# chrl.net
KiCad netlist of a schematic drawn in EAGLE
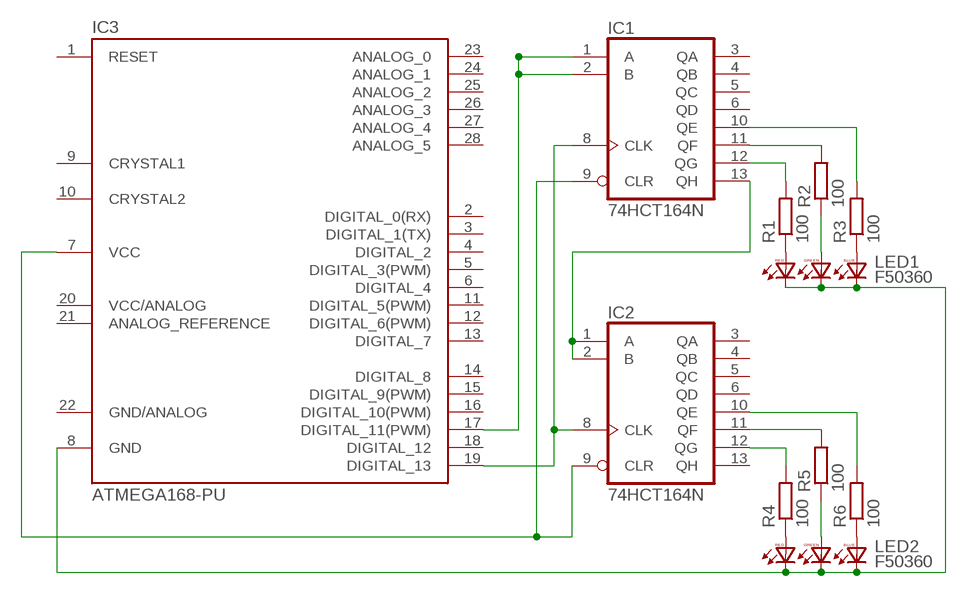
[diagram p0: schematic, sheet 1]

(export (version "E")
  (design (tool "Eeschema 10.0.6"))
  (components
    (comp (ref "IC1")
      (value "74HCT164N")
      (footprint "eagle-import:DIL14")
      (libsource (lib "eagle-import") (part "74164NHCT"))
    )
    (comp (ref "IC2")
      (value "74HCT164N")
      (footprint "eagle-import:DIL14")
      (libsource (lib "eagle-import") (part "74164NHCT"))
    )
    (comp (ref "IC3")
      (value "ATMEGA168-PU")
      (footprint "eagle-import:DIL28-3")
      (libsource (lib "eagle-import") (part "ATMEGA168-PU"))
    )
    (comp (ref "LED1")
      (value "F50360")
      (footprint "eagle-import:F50360")
      (libsource (lib "eagle-import") (part "F50360"))
    )
    (comp (ref "LED2")
      (value "F50360")
      (footprint "eagle-import:F50360")
      (libsource (lib "eagle-import") (part "F50360"))
    )
    (comp (ref "R1")
      (value "100")
      (footprint "eagle-import:0204_7")
      (libsource (lib "eagle-import") (part "R-EU_0204/7"))
    )
    (comp (ref "R2")
      (value "100")
      (footprint "eagle-import:0204_7")
      (libsource (lib "eagle-import") (part "R-EU_0204/7"))
    )
    (comp (ref "R3")
      (value "100")
      (footprint "eagle-import:0204_7")
      (libsource (lib "eagle-import") (part "R-EU_0204/7"))
    )
    (comp (ref "R4")
      (value "100")
      (footprint "eagle-import:0204_7")
      (libsource (lib "eagle-import") (part "R-EU_0204/7"))
    )
    (comp (ref "R5")
      (value "100")
      (footprint "eagle-import:0204_7")
      (libsource (lib "eagle-import") (part "R-EU_0204/7"))
    )
    (comp (ref "R6")
      (value "100")
      (footprint "eagle-import:0204_7")
      (libsource (lib "eagle-import") (part "R-EU_0204/7"))
    )
  )
  (nets
    (net (code "1") (name "/GND{slash}ANALOG") (class "Default")
      (node (ref "IC3") (pin "22") (pinfunction "GND/ANALOG_22") (pintype "power_in"))
    )
    (net (code "2") (name "Net-(IC1A-A)") (class "Default")
      (node (ref "IC1") (pin "1") (pinfunction "A_1") (pintype "input"))
      (node (ref "IC1") (pin "2") (pinfunction "B_2") (pintype "input"))
      (node (ref "IC3") (pin "17") (pinfunction "DIGITAL_11(PWM)_17") (pintype "bidirectional"))
    )
    (net (code "3") (name "Net-(IC1A-CLK)") (class "Default")
      (node (ref "IC1") (pin "8") (pinfunction "CLK_8") (pintype "input"))
      (node (ref "IC2") (pin "8") (pinfunction "CLK_8") (pintype "input"))
      (node (ref "IC3") (pin "19") (pinfunction "DIGITAL_13_19") (pintype "bidirectional"))
    )
    (net (code "4") (name "Net-(IC1A-CLR)") (class "Default")
      (node (ref "IC1") (pin "9") (pinfunction "CLR_9") (pintype "input"))
      (node (ref "IC2") (pin "9") (pinfunction "CLR_9") (pintype "input"))
      (node (ref "IC3") (pin "7") (pinfunction "VCC_7") (pintype "power_in"))
    )
    (net (code "5") (name "Net-(IC1A-QE)") (class "Default")
      (node (ref "IC1") (pin "10") (pinfunction "QE_10") (pintype "output"))
      (node (ref "R3") (pin "2") (pinfunction "2_2") (pintype "passive"))
    )
    (net (code "6") (name "Net-(IC1A-QF)") (class "Default")
      (node (ref "IC1") (pin "11") (pinfunction "QF_11") (pintype "output"))
      (node (ref "R2") (pin "2") (pinfunction "2_2") (pintype "passive"))
    )
    (net (code "7") (name "Net-(IC1A-QG)") (class "Default")
      (node (ref "IC1") (pin "12") (pinfunction "QG_12") (pintype "output"))
      (node (ref "R1") (pin "2") (pinfunction "2_2") (pintype "passive"))
    )
    (net (code "8") (name "Net-(IC1A-QH)") (class "Default")
      (node (ref "IC1") (pin "13") (pinfunction "QH_13") (pintype "output"))
      (node (ref "IC2") (pin "1") (pinfunction "A_1") (pintype "input"))
      (node (ref "IC2") (pin "2") (pinfunction "B_2") (pintype "input"))
    )
    (net (code "9") (name "Net-(IC2A-QE)") (class "Default")
      (node (ref "IC2") (pin "10") (pinfunction "QE_10") (pintype "output"))
      (node (ref "R6") (pin "2") (pinfunction "2_2") (pintype "passive"))
    )
    (net (code "10") (name "Net-(IC2A-QF)") (class "Default")
      (node (ref "IC2") (pin "11") (pinfunction "QF_11") (pintype "output"))
      (node (ref "R5") (pin "2") (pinfunction "2_2") (pintype "passive"))
    )
    (net (code "11") (name "Net-(IC2A-QG)") (class "Default")
      (node (ref "IC2") (pin "12") (pinfunction "QG_12") (pintype "output"))
      (node (ref "R4") (pin "2") (pinfunction "2_2") (pintype "passive"))
    )
    (net (code "12") (name "Net-(IC3-GND)") (class "Default")
      (node (ref "IC3") (pin "8") (pinfunction "GND_8") (pintype "power_in"))
      (node (ref "LED1") (pin "BC") (pinfunction "BC_BC") (pintype "passive"))
      (node (ref "LED1") (pin "GC") (pinfunction "GC_GC") (pintype "passive"))
      (node (ref "LED1") (pin "RC") (pinfunction "RC_RC") (pintype "passive"))
      (node (ref "LED2") (pin "BC") (pinfunction "BC_BC") (pintype "passive"))
      (node (ref "LED2") (pin "GC") (pinfunction "GC_GC") (pintype "passive"))
      (node (ref "LED2") (pin "RC") (pinfunction "RC_RC") (pintype "passive"))
    )
    (net (code "13") (name "Net-(LED1-PadBA)") (class "Default")
      (node (ref "LED1") (pin "BA") (pinfunction "BA_BA") (pintype "passive"))
      (node (ref "R3") (pin "1") (pinfunction "1_1") (pintype "passive"))
    )
    (net (code "14") (name "Net-(LED1-PadGA)") (class "Default")
      (node (ref "LED1") (pin "GA") (pinfunction "GA_GA") (pintype "passive"))
      (node (ref "R2") (pin "1") (pinfunction "1_1") (pintype "passive"))
    )
    (net (code "15") (name "Net-(LED1-PadRA)") (class "Default")
      (node (ref "LED1") (pin "RA") (pinfunction "RA_RA") (pintype "passive"))
      (node (ref "R1") (pin "1") (pinfunction "1_1") (pintype "passive"))
    )
    (net (code "16") (name "Net-(LED2-PadBA)") (class "Default")
      (node (ref "LED2") (pin "BA") (pinfunction "BA_BA") (pintype "passive"))
      (node (ref "R6") (pin "1") (pinfunction "1_1") (pintype "passive"))
    )
    (net (code "17") (name "Net-(LED2-PadGA)") (class "Default")
      (node (ref "LED2") (pin "GA") (pinfunction "GA_GA") (pintype "passive"))
      (node (ref "R5") (pin "1") (pinfunction "1_1") (pintype "passive"))
    )
    (net (code "18") (name "Net-(LED2-PadRA)") (class "Default")
      (node (ref "LED2") (pin "RA") (pinfunction "RA_RA") (pintype "passive"))
      (node (ref "R4") (pin "1") (pinfunction "1_1") (pintype "passive"))
    )
    (net (code "19") (name "unconnected-(IC1A-QA-Pad3)") (class "Default")
      (node (ref "IC1") (pin "3") (pinfunction "QA_3") (pintype "output"))
    )
    (net (code "20") (name "unconnected-(IC1A-QB-Pad4)") (class "Default")
      (node (ref "IC1") (pin "4") (pinfunction "QB_4") (pintype "output"))
    )
    (net (code "21") (name "unconnected-(IC1A-QC-Pad5)") (class "Default")
      (node (ref "IC1") (pin "5") (pinfunction "QC_5") (pintype "output"))
    )
    (net (code "22") (name "unconnected-(IC1A-QD-Pad6)") (class "Default")
      (node (ref "IC1") (pin "6") (pinfunction "QD_6") (pintype "output"))
    )
    (net (code "23") (name "unconnected-(IC2A-QA-Pad3)") (class "Default")
      (node (ref "IC2") (pin "3") (pinfunction "QA_3") (pintype "output"))
    )
    (net (code "24") (name "unconnected-(IC2A-QB-Pad4)") (class "Default")
      (node (ref "IC2") (pin "4") (pinfunction "QB_4") (pintype "output"))
    )
    (net (code "25") (name "unconnected-(IC2A-QC-Pad5)") (class "Default")
      (node (ref "IC2") (pin "5") (pinfunction "QC_5") (pintype "output"))
    )
    (net (code "26") (name "unconnected-(IC2A-QD-Pad6)") (class "Default")
      (node (ref "IC2") (pin "6") (pinfunction "QD_6") (pintype "output"))
    )
    (net (code "27") (name "unconnected-(IC2A-QH-Pad13)") (class "Default")
      (node (ref "IC2") (pin "13") (pinfunction "QH_13") (pintype "output"))
    )
    (net (code "28") (name "unconnected-(IC3-ANALOG_0-Pad23)") (class "Default")
      (node (ref "IC3") (pin "23") (pinfunction "ANALOG_0_23") (pintype "bidirectional"))
    )
    (net (code "29") (name "unconnected-(IC3-ANALOG_1-Pad24)") (class "Default")
      (node (ref "IC3") (pin "24") (pinfunction "ANALOG_1_24") (pintype "bidirectional"))
    )
    (net (code "30") (name "unconnected-(IC3-ANALOG_2-Pad25)") (class "Default")
      (node (ref "IC3") (pin "25") (pinfunction "ANALOG_2_25") (pintype "bidirectional"))
    )
    (net (code "31") (name "unconnected-(IC3-ANALOG_3-Pad26)") (class "Default")
      (node (ref "IC3") (pin "26") (pinfunction "ANALOG_3_26") (pintype "bidirectional"))
    )
    (net (code "32") (name "unconnected-(IC3-ANALOG_4-Pad27)") (class "Default")
      (node (ref "IC3") (pin "27") (pinfunction "ANALOG_4_27") (pintype "bidirectional"))
    )
    (net (code "33") (name "unconnected-(IC3-ANALOG_5-Pad28)") (class "Default")
      (node (ref "IC3") (pin "28") (pinfunction "ANALOG_5_28") (pintype "bidirectional"))
    )
    (net (code "34") (name "unconnected-(IC3-ANALOG_REFERENCE-Pad21)") (class "Default")
      (node (ref "IC3") (pin "21") (pinfunction "ANALOG_REFERENCE_21") (pintype "passive"))
    )
    (net (code "35") (name "unconnected-(IC3-CRYSTAL1-Pad9)") (class "Default")
      (node (ref "IC3") (pin "9") (pinfunction "CRYSTAL1_9") (pintype "bidirectional"))
    )
    (net (code "36") (name "unconnected-(IC3-CRYSTAL2-Pad10)") (class "Default")
      (node (ref "IC3") (pin "10") (pinfunction "CRYSTAL2_10") (pintype "bidirectional"))
    )
    (net (code "37") (name "unconnected-(IC3-DIGITAL_0(RX)-Pad2)") (class "Default")
      (node (ref "IC3") (pin "2") (pinfunction "DIGITAL_0(RX)_2") (pintype "bidirectional"))
    )
    (net (code "38") (name "unconnected-(IC3-DIGITAL_1(TX)-Pad3)") (class "Default")
      (node (ref "IC3") (pin "3") (pinfunction "DIGITAL_1(TX)_3") (pintype "bidirectional"))
    )
    (net (code "39") (name "unconnected-(IC3-DIGITAL_2-Pad4)") (class "Default")
      (node (ref "IC3") (pin "4") (pinfunction "DIGITAL_2_4") (pintype "bidirectional"))
    )
    (net (code "40") (name "unconnected-(IC3-DIGITAL_3(PWM)-Pad5)") (class "Default")
      (node (ref "IC3") (pin "5") (pinfunction "DIGITAL_3(PWM)_5") (pintype "bidirectional"))
    )
    (net (code "41") (name "unconnected-(IC3-DIGITAL_4-Pad6)") (class "Default")
      (node (ref "IC3") (pin "6") (pinfunction "DIGITAL_4_6") (pintype "bidirectional"))
    )
    (net (code "42") (name "unconnected-(IC3-DIGITAL_5(PWM)-Pad11)") (class "Default")
      (node (ref "IC3") (pin "11") (pinfunction "DIGITAL_5(PWM)_11") (pintype "bidirectional"))
    )
    (net (code "43") (name "unconnected-(IC3-DIGITAL_6(PWM)-Pad12)") (class "Default")
      (node (ref "IC3") (pin "12") (pinfunction "DIGITAL_6(PWM)_12") (pintype "bidirectional"))
    )
    (net (code "44") (name "unconnected-(IC3-DIGITAL_7-Pad13)") (class "Default")
      (node (ref "IC3") (pin "13") (pinfunction "DIGITAL_7_13") (pintype "bidirectional"))
    )
    (net (code "45") (name "unconnected-(IC3-DIGITAL_8-Pad14)") (class "Default")
      (node (ref "IC3") (pin "14") (pinfunction "DIGITAL_8_14") (pintype "bidirectional"))
    )
    (net (code "46") (name "unconnected-(IC3-DIGITAL_9(PWM)-Pad15)") (class "Default")
      (node (ref "IC3") (pin "15") (pinfunction "DIGITAL_9(PWM)_15") (pintype "bidirectional"))
    )
    (net (code "47") (name "unconnected-(IC3-DIGITAL_10(PWM)-Pad16)") (class "Default")
      (node (ref "IC3") (pin "16") (pinfunction "DIGITAL_10(PWM)_16") (pintype "bidirectional"))
    )
    (net (code "48") (name "unconnected-(IC3-DIGITAL_12-Pad18)") (class "Default")
      (node (ref "IC3") (pin "18") (pinfunction "DIGITAL_12_18") (pintype "bidirectional"))
    )
    (net (code "49") (name "unconnected-(IC3-RESET-Pad1)") (class "Default")
      (node (ref "IC3") (pin "1") (pinfunction "RESET_1") (pintype "bidirectional"))
    )
    (net (code "50") (name "unconnected-(IC3-VCC{slash}ANALOG-Pad20)") (class "Default")
      (node (ref "IC3") (pin "20") (pinfunction "VCC/ANALOG_20") (pintype "passive"))
    )
  )
)
